# Stabilizer.net
KiCad netlist of a schematic drawn in Altium Designer
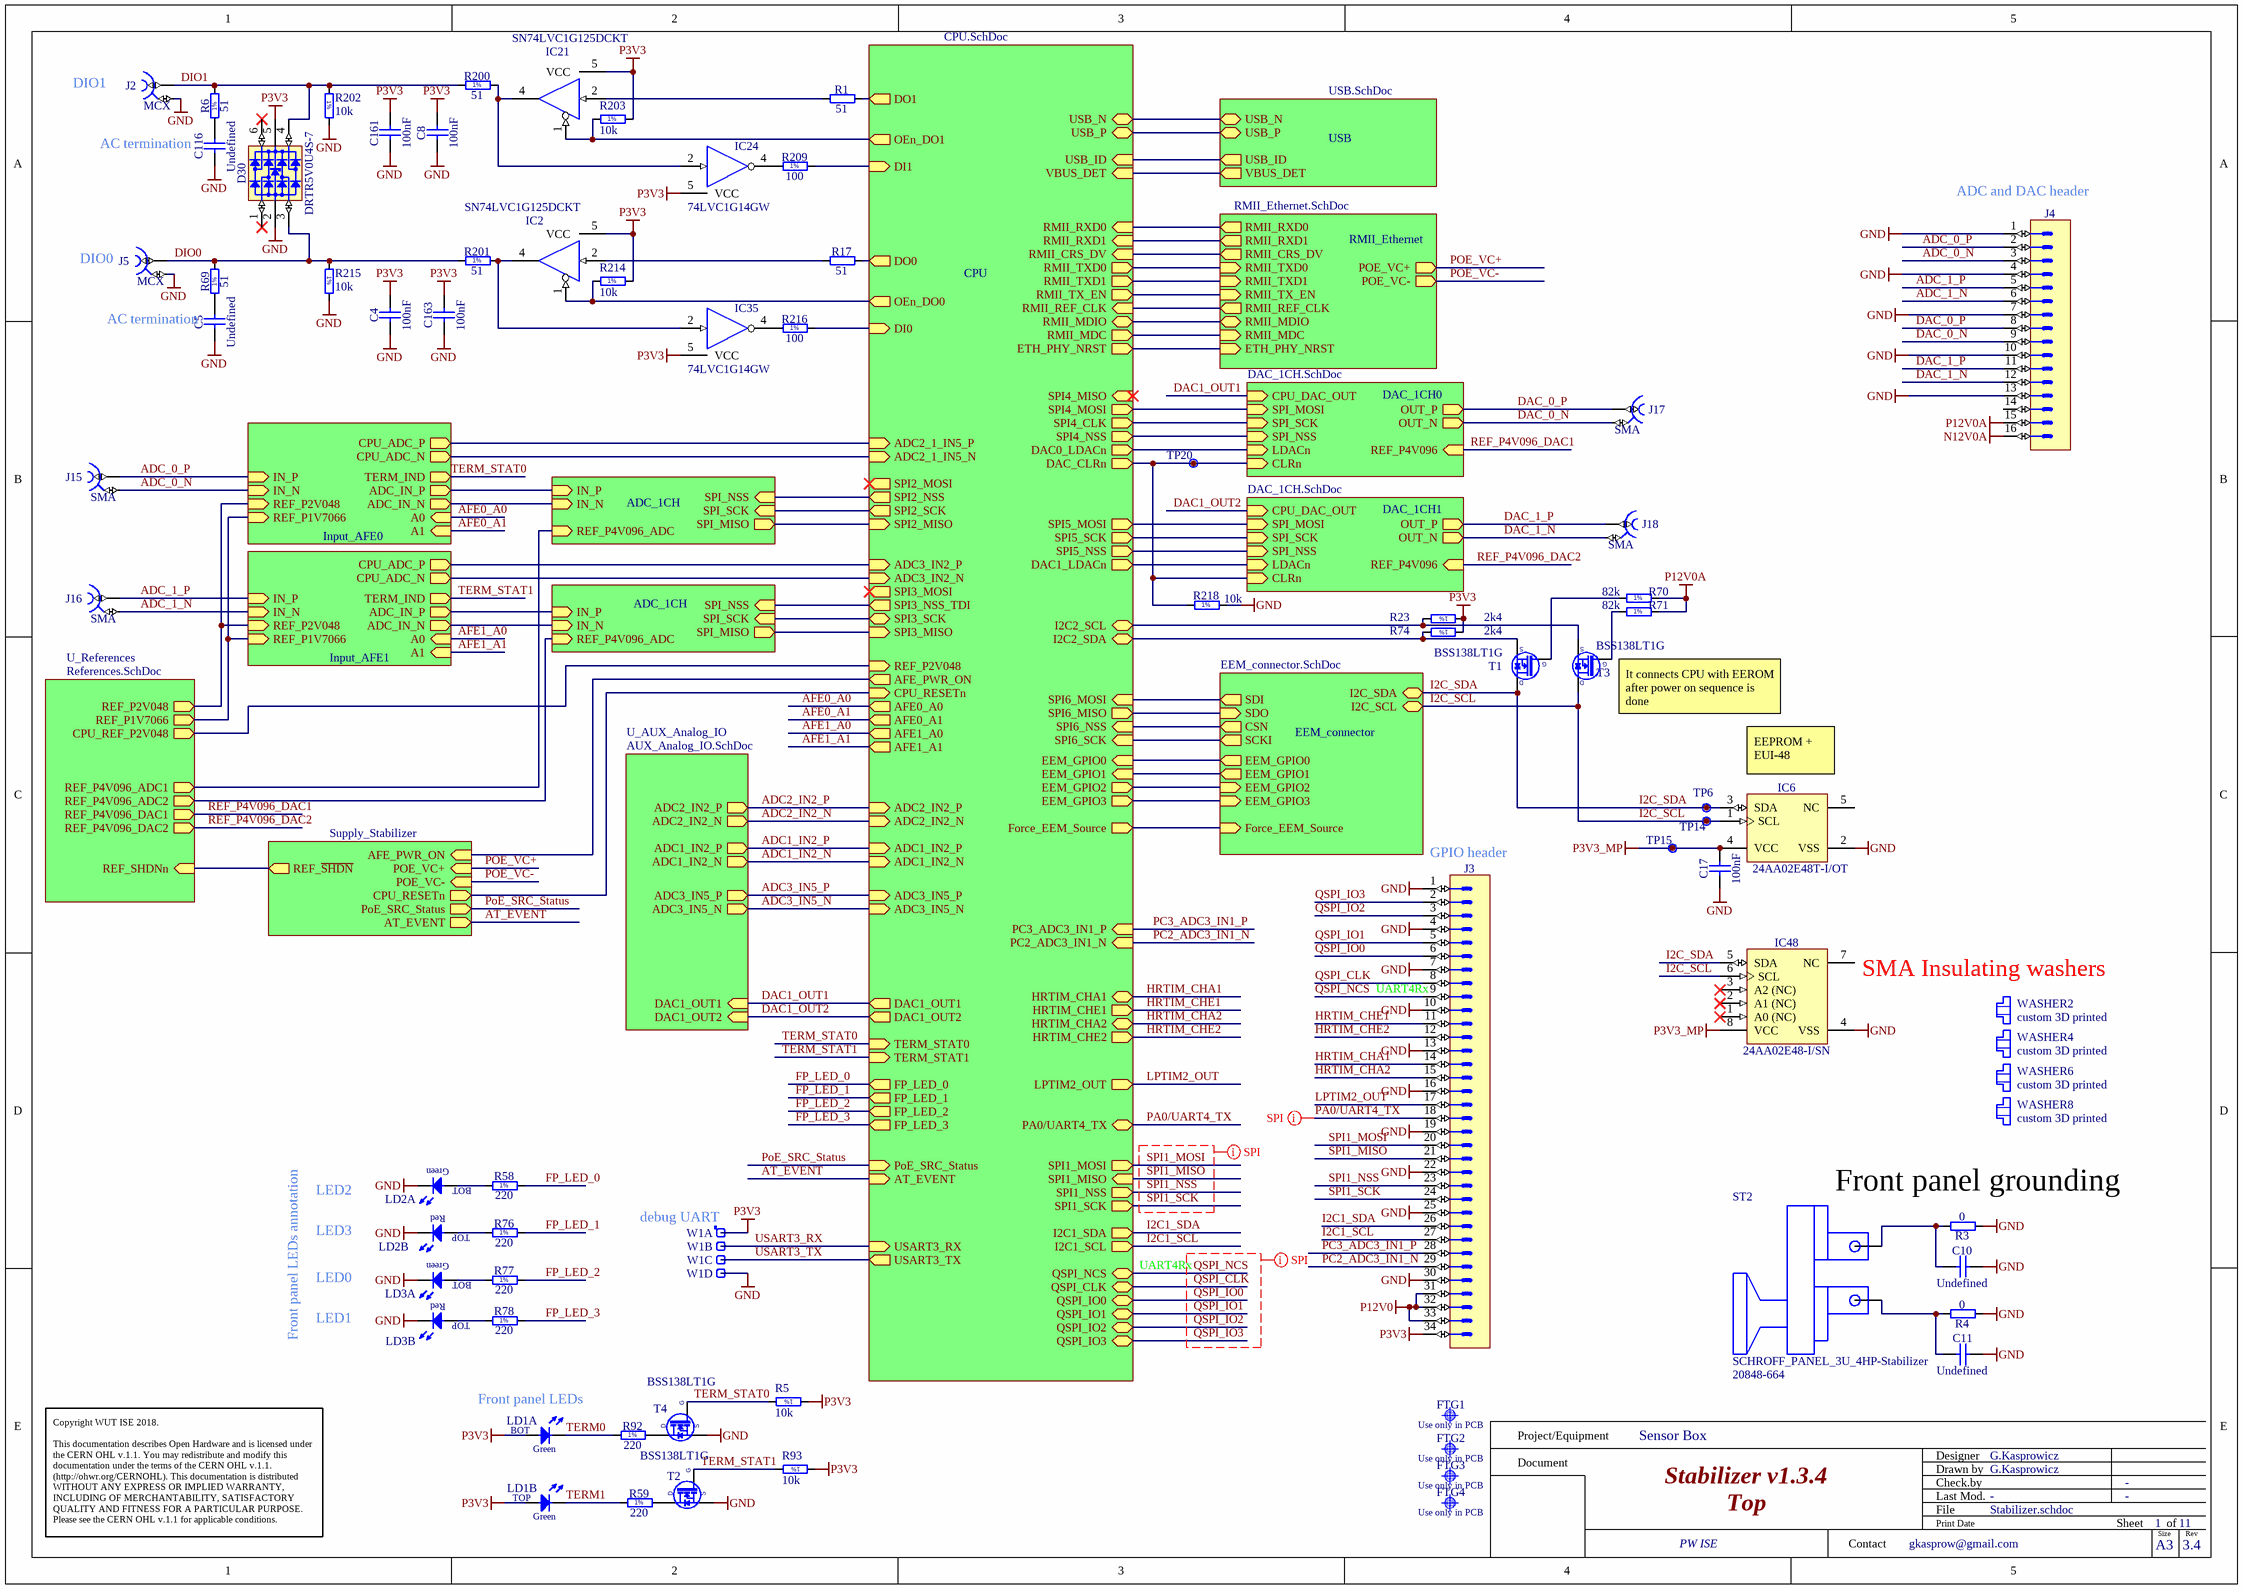
[diagram p0: Stabilizer.schdoc]

(export (version "E")
  (design (tool "Eeschema 10.0.6"))
  (components
    (comp (ref "C4")
      (value "100nF")
      (footprint "CAPC1005X55N")
      (description "Non-polarised capacitor")
      (fields
        (field (name "PART NUMBER") "CC0402_100NF_16V_10%_X7R")
        (field (name "VOLTAGE") "16V")
        (field (name "AUTHOR") "CERN DEM JLC")
      )
      (libsource (lib "Capacitors") (part "Capacitor - non polarized"))
    )
    (comp (ref "C5")
      (value "Undefined")
      (footprint "CAPC1608X90N")
      (description "Non-polarised capacitor")
      (fields (field (name "PART NUMBER") "CC0603_NO-VALUE") (field (name "AUTHOR") "CERN DEM MR"))
      (libsource (lib "Capacitors") (part "Capacitor - non polarized"))
    )
    (comp (ref "C8")
      (value "100nF")
      (footprint "CAPC1005X55N")
      (description "Non-polarised capacitor")
      (fields
        (field (name "PART NUMBER") "CC0402_100NF_16V_10%_X7R")
        (field (name "VOLTAGE") "16V")
        (field (name "AUTHOR") "CERN DEM JLC")
      )
      (libsource (lib "Capacitors") (part "Capacitor - non polarized"))
    )
    (comp (ref "C10")
      (value "Undefined")
      (footprint "CAPC2012X135N")
      (description "Non-polarised capacitor")
      (fields (field (name "PART NUMBER") "CC0805_NO-VALUE") (field (name "AUTHOR") "CERN DEM JLC"))
      (libsource (lib "Capacitors") (part "Capacitor - non polarized"))
    )
    (comp (ref "C11")
      (value "Undefined")
      (footprint "CAPC2012X135N")
      (description "Non-polarised capacitor")
      (fields (field (name "PART NUMBER") "CC0805_NO-VALUE") (field (name "AUTHOR") "CERN DEM JLC"))
      (libsource (lib "Capacitors") (part "Capacitor - non polarized"))
    )
    (comp (ref "C17")
      (value "100nF")
      (footprint "CAPC1005X55N")
      (description "Non-polarised capacitor")
      (fields
        (field (name "PART NUMBER") "CC0402_100NF_16V_10%_X5R")
        (field (name "VOLTAGE") "16V")
        (field (name "AUTHOR") "CERN DEM JLC")
      )
      (libsource (lib "Capacitors") (part "Capacitor - non polarized"))
    )
    (comp (ref "C116")
      (value "Undefined")
      (footprint "CAPC1608X90N")
      (description "Non-polarised capacitor")
      (fields (field (name "PART NUMBER") "CC0603_NO-VALUE") (field (name "AUTHOR") "CERN DEM MR"))
      (libsource (lib "Capacitors") (part "Capacitor - non polarized"))
    )
    (comp (ref "C161")
      (value "100nF")
      (footprint "CAPC1005X55N")
      (description "Non-polarised capacitor")
      (fields
        (field (name "PART NUMBER") "CC0402_100NF_16V_10%_X7R")
        (field (name "VOLTAGE") "16V")
        (field (name "AUTHOR") "CERN DEM JLC")
      )
      (libsource (lib "Capacitors") (part "Capacitor - non polarized"))
    )
    (comp (ref "C163")
      (value "100nF")
      (footprint "CAPC1005X55N")
      (description "Non-polarised capacitor")
      (fields
        (field (name "PART NUMBER") "CC0402_100NF_16V_10%_X7R")
        (field (name "VOLTAGE") "16V")
        (field (name "AUTHOR") "CERN DEM JLC")
      )
      (libsource (lib "Capacitors") (part "Capacitor - non polarized"))
    )
    (comp (ref "D30")
      (value "DRTR5V0U4S-7")
      (footprint "SOT65P210X110-6N")
      (description "Integrated Quad Ultra-Low Capacitance ESD Protection")
      (fields (field (name "MANUFACTURER") "DIODES") (field (name "AUTHOR") "GK"))
      (libsource (lib "Diodes") (part "D_TVS_DRTR5V0U4S-7"))
    )
    (comp (ref "FTG1")
      (value "Use only in PCB")
      (footprint "FIDUCIAL_TOP_C100-200")
      (description "Fiducial Target")
      (fields (field (name "PART NUMBER") "FIDUCIAL_TARGET_C100-200") (field (name "AUTHOR") "CERN DEM JLC"))
      (libsource (lib "Eletro-mechanical") (part "Fiducial Target"))
    )
    (comp (ref "FTG2")
      (value "Use only in PCB")
      (footprint "FIDUCIAL_TOP_S100-200")
      (description "Fiducial Target")
      (fields (field (name "PART NUMBER") "FIDUCIAL_TARGET_S100-200") (field (name "AUTHOR") "CERN DEM JLC"))
      (libsource (lib "Eletro-mechanical") (part "Fiducial Target"))
    )
    (comp (ref "FTG3")
      (value "Use only in PCB")
      (footprint "FIDUCIAL_TOP_S100-200")
      (description "Fiducial Target")
      (fields (field (name "PART NUMBER") "FIDUCIAL_TARGET_S100-200") (field (name "AUTHOR") "CERN DEM JLC"))
      (libsource (lib "Eletro-mechanical") (part "Fiducial Target"))
    )
    (comp (ref "FTG4")
      (value "Use only in PCB")
      (footprint "FIDUCIAL_TOP_S100-200")
      (description "Fiducial Target")
      (fields (field (name "PART NUMBER") "FIDUCIAL_TARGET_S100-200") (field (name "AUTHOR") "CERN DEM JLC"))
      (libsource (lib "Eletro-mechanical") (part "Fiducial Target"))
    )
    (comp (ref "IC2")
      (value "SN74LVC1G125DCKT")
      (footprint "SOT65P210X110-5N")
      (description "Single Bus Buffer Gate With 3-State Output")
      (fields (field (name "MANUFACTURER") "TEXAS INSTRUMENTS") (field (name "AUTHOR") "CERN DEM JLC"))
      (libsource (lib "ICs And Semiconductors") (part "741G125"))
    )
    (comp (ref "IC6")
      (value "24AA02E48T-I/OT")
      (footprint "SOT95P280X145-5N")
      (description "1.7V-5.5V, 2K I2C Serial EEPROM With EUI-48 Node Identity")
      (fields (field (name "MANUFACTURER") "MICROCHIP TECHNOLOGY") (field (name "AUTHOR") "CERN DEM MR"))
      (libsource (lib "ICs And Semiconductors") (part "24AA02E48T-I/OT"))
    )
    (comp (ref "IC21")
      (value "SN74LVC1G125DCKT")
      (footprint "SOT65P210X110-5N")
      (description "Single Bus Buffer Gate With 3-State Output")
      (fields (field (name "MANUFACTURER") "TEXAS INSTRUMENTS") (field (name "AUTHOR") "CERN DEM JLC"))
      (libsource (lib "ICs And Semiconductors") (part "741G125"))
    )
    (comp (ref "IC24")
      (value "74LVC1G14GW")
      (footprint "SOT65P212X110-5N")
      (description "Single Schmitt-Trigger Inverter")
      (fields (field (name "MANUFACTURER") "NXP SEMICONDUCTORS") (field (name "AUTHOR") "CERN DEM JLC"))
      (libsource (lib "ICs And Semiconductors") (part "741G14"))
    )
    (comp (ref "IC35")
      (value "74LVC1G14GW")
      (footprint "SOT65P212X110-5N")
      (description "Single Schmitt-Trigger Inverter")
      (fields (field (name "MANUFACTURER") "NXP SEMICONDUCTORS") (field (name "AUTHOR") "CERN DEM JLC"))
      (libsource (lib "ICs And Semiconductors") (part "741G14"))
    )
    (comp (ref "IC48")
      (value "24AA02E48-I/SN")
      (footprint "SOIC127P600X175-8N")
      (description "1.7V-5.5V, 2K I2C™ Serial EEPROMs with EUI-48™ Node Identity")
      (fields (field (name "MANUFACTURER") "MICROCHIP TECHNOLOGY") (field (name "AUTHOR") "CERN DEM MR"))
      (libsource (lib "ICS-logic") (part "MEM_24AA02E48-I/SN"))
    )
    (comp (ref "J2")
      (value "MCX")
      (footprint "AMPHENOL_919-383J-51A")
      (fields
        (field (name "PART NUMBER") "AMPHENOL_919-383J-51A")
        (field (name "MANUFACTURER") "AMPHENOL")
        (field (name "MANUFACTURER PART NUMBER") "919-383J-51A")
        (field (name "AUTHOR") "CERN DEM BC")
      )
      (libsource (lib "Connectors") (part "Coax_1Female_1Shield"))
    )
    (comp (ref "J3")
      (value "Use original!")
      (footprint "3M_N2534-6002RB")
      (description "Connector 34 Male")
      (fields
        (field (name "PART NUMBER") "Use original!  3M_N2534-6002RB")
        (field (name "MANUFACTURER") "3M")
        (field (name "AUTHOR") "CERN DEM JLC")
      )
      (libsource (lib "Connectors") (part "Connector 34 Male"))
    )
    (comp (ref "J4")
      (value "Use original!")
      (footprint "3M_N2516-6002RB")
      (description "Connector 16 Male")
      (fields
        (field (name "PART NUMBER") "Use original!  3M_N2516-6002RB")
        (field (name "MANUFACTURER") "3M")
        (field (name "AUTHOR") "CERN DEM JLC")
      )
      (libsource (lib "Connectors") (part "Connector 16 Male"))
    )
    (comp (ref "J5")
      (value "MCX")
      (footprint "AMPHENOL_919-383J-51A")
      (fields
        (field (name "PART NUMBER") "AMPHENOL_919-383J-51A")
        (field (name "MANUFACTURER") "AMPHENOL")
        (field (name "MANUFACTURER PART NUMBER") "919-383J-51A")
        (field (name "AUTHOR") "CERN DEM BC")
      )
      (libsource (lib "Connectors") (part "Coax_1Female_1Shield"))
    )
    (comp (ref "J15")
      (value "SMA")
      (footprint "DELOCK_65848")
      (description "50 Ohm Through Hole SMA Right Angle PCB Jack")
      (fields
        (field (name "PART NUMBER") "DELOCK_65848")
        (field (name "MANUFACTURER") "DELOCK")
        (field (name "AUTHOR") "GK")
      )
      (libsource (lib "Connectors") (part "CON_SMA_DELOCK_65848"))
    )
    (comp (ref "J16")
      (value "SMA")
      (footprint "DELOCK_65848")
      (description "50 Ohm Through Hole SMA Right Angle PCB Jack")
      (fields
        (field (name "PART NUMBER") "DELOCK_65848")
        (field (name "MANUFACTURER") "DELOCK")
        (field (name "AUTHOR") "GK")
      )
      (libsource (lib "Connectors") (part "CON_SMA_DELOCK_65848"))
    )
    (comp (ref "J17")
      (value "SMA")
      (footprint "DELOCK_65848")
      (description "50 Ohm Through Hole SMA Right Angle PCB Jack")
      (fields
        (field (name "PART NUMBER") "DELOCK_65848")
        (field (name "MANUFACTURER") "DELOCK")
        (field (name "AUTHOR") "GK")
      )
      (libsource (lib "") (part "CON_SMA_DELOCK_65848_1"))
    )
    (comp (ref "J18")
      (value "SMA")
      (footprint "DELOCK_65848")
      (description "50 Ohm Through Hole SMA Right Angle PCB Jack")
      (fields
        (field (name "PART NUMBER") "DELOCK_65848")
        (field (name "MANUFACTURER") "DELOCK")
        (field (name "AUTHOR") "GK")
      )
      (libsource (lib "") (part "CON_SMA_DELOCK_65848_1"))
    )
    (comp (ref "LD1")
      (value "Green/Green")
      (footprint "LED_DIALIGHT_571-0122F")
      (description "LED x2 Green 1C2A-BOT_3C4A-TOP")
      (fields
        (field (name "PART NUMBER") "LED_DIALIGHT_571-0122F")
        (field (name "MANUFACTURER") "DIALIGHT")
        (field (name "AUTHOR") "CERN DEM JLC")
      )
      (libsource (lib "ICs And Semiconductors") (part "LED x2 Green 1C2A-BOT_3C4A-TOP"))
    )
    (comp (ref "LD2")
      (value "Red/Green")
      (footprint "LED_DIALIGHT_571-0112F")
      (description "2x LED  Botom Green, Top Red")
      (fields
        (field (name "PART NUMBER") "LED_DIALIGHT_571-0112F")
        (field (name "MANUFACTURER") "DIALIGHT")
        (field (name "AUTHOR") "CERN DEM JLC")
      )
      (libsource (lib "ICs And Semiconductors") (part "LED x2 G-1C2A-BOT_R-3C4A-TOP"))
    )
    (comp (ref "LD3")
      (value "Red/Green")
      (footprint "LED_DIALIGHT_571-0112F")
      (description "2x LED  Botom Green, Top Red")
      (fields
        (field (name "PART NUMBER") "LED_DIALIGHT_571-0112F")
        (field (name "MANUFACTURER") "DIALIGHT")
        (field (name "AUTHOR") "CERN DEM JLC")
      )
      (libsource (lib "ICs And Semiconductors") (part "LED x2 G-1C2A-BOT_R-3C4A-TOP"))
    )
    (comp (ref "R1")
      (value "51")
      (footprint "RESC1005X40N")
      (description "Resistor - 1%")
      (fields
        (field (name "PART NUMBER") "R0402_51R_1%_0.0625W_100PPM")
        (field (name "POWER") "0.0625W")
        (field (name "AUTHOR") "CERN DEM JLC")
      )
      (libsource (lib "Resistors") (part "Resistor - 1%"))
    )
    (comp (ref "R3")
      (value "0")
      (footprint "RESC1608X55N")
      (description "Resistor")
      (fields
        (field (name "PART NUMBER") "R0603_0R_JUMPER")
        (field (name "MANUFACTURER") "GENERIC")
        (field (name "AUTHOR") "CERN DEM JLC")
      )
      (libsource (lib "Resistors") (part "Resistor"))
    )
    (comp (ref "R4")
      (value "0")
      (footprint "RESC1608X55N")
      (description "Resistor")
      (fields
        (field (name "PART NUMBER") "R0603_0R_JUMPER")
        (field (name "MANUFACTURER") "GENERIC")
        (field (name "AUTHOR") "CERN DEM JLC")
      )
      (libsource (lib "Resistors") (part "Resistor"))
    )
    (comp (ref "R5")
      (value "10k")
      (footprint "RESC1005X40N")
      (description "Resistor - 1%")
      (fields
        (field (name "PART NUMBER") "R0402_10K_1%_0.0625W_100PPM")
        (field (name "POWER") "0.0625W")
        (field (name "AUTHOR") "CERN DEM JLC")
      )
      (libsource (lib "Resistors") (part "Resistor - 1%"))
    )
    (comp (ref "R6")
      (value "51")
      (footprint "RESC1005X40N")
      (description "Resistor - 1%")
      (fields
        (field (name "PART NUMBER") "R0402_51R_1%_0.0625W_100PPM")
        (field (name "POWER") "0.0625W")
        (field (name "AUTHOR") "CERN DEM JLC")
      )
      (libsource (lib "Resistors") (part "Resistor - 1%"))
    )
    (comp (ref "R17")
      (value "51")
      (footprint "RESC1005X40N")
      (description "Resistor - 1%")
      (fields
        (field (name "PART NUMBER") "R0402_51R_1%_0.0625W_100PPM")
        (field (name "POWER") "0.0625W")
        (field (name "AUTHOR") "CERN DEM JLC")
      )
      (libsource (lib "Resistors") (part "Resistor - 1%"))
    )
    (comp (ref "R23")
      (value "2k4")
      (footprint "RESC1005X40N")
      (description "Resistor - 1%")
      (fields
        (field (name "PART NUMBER") "R0402_2K4_1%_0.0625W_100PPM")
        (field (name "POWER") "0.0625W")
        (field (name "AUTHOR") "CERN DEM JLC")
      )
      (libsource (lib "Resistors") (part "Resistor - 1%"))
    )
    (comp (ref "R58")
      (value "220")
      (footprint "RESC1608X55N")
      (description "Resistor - 1%")
      (fields
        (field (name "PART NUMBER") "R0603_220R_1%_0.1W_100PPM")
        (field (name "POWER") "0.1W")
        (field (name "AUTHOR") "CERN DEM JLC")
      )
      (libsource (lib "Resistors") (part "Resistor - 1%"))
    )
    (comp (ref "R59")
      (value "220")
      (footprint "RESC1608X55N")
      (description "Resistor - 1%")
      (fields
        (field (name "PART NUMBER") "R0603_220R_1%_0.1W_100PPM")
        (field (name "POWER") "0.1W")
        (field (name "AUTHOR") "CERN DEM JLC")
      )
      (libsource (lib "Resistors") (part "Resistor - 1%"))
    )
    (comp (ref "R69")
      (value "51")
      (footprint "RESC1005X40N")
      (description "Resistor - 1%")
      (fields
        (field (name "PART NUMBER") "R0402_51R_1%_0.0625W_100PPM")
        (field (name "POWER") "0.0625W")
        (field (name "AUTHOR") "CERN DEM JLC")
      )
      (libsource (lib "Resistors") (part "Resistor - 1%"))
    )
    (comp (ref "R70")
      (value "82k")
      (footprint "RESC1608X55N")
      (description "Resistor - 1%")
      (fields
        (field (name "PART NUMBER") "R0603_82K_1%_0.1W_100PPM")
        (field (name "POWER") "0.1W")
        (field (name "AUTHOR") "CERN DEM JLC")
      )
      (libsource (lib "Resistors") (part "Resistor - 1%"))
    )
    (comp (ref "R71")
      (value "82k")
      (footprint "RESC1608X55N")
      (description "Resistor - 1%")
      (fields
        (field (name "PART NUMBER") "R0603_82K_1%_0.1W_100PPM")
        (field (name "POWER") "0.1W")
        (field (name "AUTHOR") "CERN DEM JLC")
      )
      (libsource (lib "Resistors") (part "Resistor - 1%"))
    )
    (comp (ref "R74")
      (value "2k4")
      (footprint "RESC1005X40N")
      (description "Resistor - 1%")
      (fields
        (field (name "PART NUMBER") "R0402_2K4_1%_0.0625W_100PPM")
        (field (name "POWER") "0.0625W")
        (field (name "AUTHOR") "CERN DEM JLC")
      )
      (libsource (lib "Resistors") (part "Resistor - 1%"))
    )
    (comp (ref "R76")
      (value "220")
      (footprint "RESC1608X55N")
      (description "Resistor - 1%")
      (fields
        (field (name "PART NUMBER") "R0603_220R_1%_0.1W_100PPM")
        (field (name "POWER") "0.1W")
        (field (name "AUTHOR") "CERN DEM JLC")
      )
      (libsource (lib "Resistors") (part "Resistor - 1%"))
    )
    (comp (ref "R77")
      (value "220")
      (footprint "RESC1608X55N")
      (description "Resistor - 1%")
      (fields
        (field (name "PART NUMBER") "R0603_220R_1%_0.1W_100PPM")
        (field (name "POWER") "0.1W")
        (field (name "AUTHOR") "CERN DEM JLC")
      )
      (libsource (lib "Resistors") (part "Resistor - 1%"))
    )
    (comp (ref "R78")
      (value "220")
      (footprint "RESC1608X55N")
      (description "Resistor - 1%")
      (fields
        (field (name "PART NUMBER") "R0603_220R_1%_0.1W_100PPM")
        (field (name "POWER") "0.1W")
        (field (name "AUTHOR") "CERN DEM JLC")
      )
      (libsource (lib "Resistors") (part "Resistor - 1%"))
    )
    (comp (ref "R92")
      (value "220")
      (footprint "RESC1608X55N")
      (description "Resistor - 1%")
      (fields
        (field (name "PART NUMBER") "R0603_220R_1%_0.1W_100PPM")
        (field (name "POWER") "0.1W")
        (field (name "AUTHOR") "CERN DEM JLC")
      )
      (libsource (lib "Resistors") (part "Resistor - 1%"))
    )
    (comp (ref "R93")
      (value "10k")
      (footprint "RESC1005X40N")
      (description "Resistor - 1%")
      (fields
        (field (name "PART NUMBER") "R0402_10K_1%_0.0625W_100PPM")
        (field (name "POWER") "0.0625W")
        (field (name "AUTHOR") "CERN DEM JLC")
      )
      (libsource (lib "Resistors") (part "Resistor - 1%"))
    )
    (comp (ref "R200")
      (value "51")
      (footprint "RESC1005X40N")
      (description "Resistor - 1%")
      (fields
        (field (name "PART NUMBER") "R0402_51R_1%_0.0625W_100PPM")
        (field (name "POWER") "0.0625W")
        (field (name "AUTHOR") "CERN DEM JLC")
      )
      (libsource (lib "Resistors") (part "Resistor - 1%"))
    )
    (comp (ref "R201")
      (value "51")
      (footprint "RESC1005X40N")
      (description "Resistor - 1%")
      (fields
        (field (name "PART NUMBER") "R0402_51R_1%_0.0625W_100PPM")
        (field (name "POWER") "0.0625W")
        (field (name "AUTHOR") "CERN DEM JLC")
      )
      (libsource (lib "Resistors") (part "Resistor - 1%"))
    )
    (comp (ref "R202")
      (value "10k")
      (footprint "RESC1005X40N")
      (description "Resistor - 1%")
      (fields
        (field (name "PART NUMBER") "R0402_10K_1%_0.0625W_100PPM")
        (field (name "POWER") "0.0625W")
        (field (name "AUTHOR") "CERN DEM JLC")
      )
      (libsource (lib "Resistors") (part "Resistor - 1%"))
    )
    (comp (ref "R203")
      (value "10k")
      (footprint "RESC1005X40N")
      (description "Resistor - 1%")
      (fields
        (field (name "PART NUMBER") "R0402_10K_1%_0.0625W_100PPM")
        (field (name "POWER") "0.0625W")
        (field (name "AUTHOR") "CERN DEM JLC")
      )
      (libsource (lib "Resistors") (part "Resistor - 1%"))
    )
    (comp (ref "R209")
      (value "100")
      (footprint "RESC1005X40N")
      (description "Resistor - 1%")
      (fields
        (field (name "PART NUMBER") "R0402_100R_1%_0.0625W_100PPM")
        (field (name "POWER") "0.0625W")
        (field (name "AUTHOR") "CERN DEM JLC")
      )
      (libsource (lib "Resistors") (part "Resistor - 1%"))
    )
    (comp (ref "R214")
      (value "10k")
      (footprint "RESC1005X40N")
      (description "Resistor - 1%")
      (fields
        (field (name "PART NUMBER") "R0402_10K_1%_0.0625W_100PPM")
        (field (name "POWER") "0.0625W")
        (field (name "AUTHOR") "CERN DEM JLC")
      )
      (libsource (lib "Resistors") (part "Resistor - 1%"))
    )
    (comp (ref "R215")
      (value "10k")
      (footprint "RESC1005X40N")
      (description "Resistor - 1%")
      (fields
        (field (name "PART NUMBER") "R0402_10K_1%_0.0625W_100PPM")
        (field (name "POWER") "0.0625W")
        (field (name "AUTHOR") "CERN DEM JLC")
      )
      (libsource (lib "Resistors") (part "Resistor - 1%"))
    )
    (comp (ref "R216")
      (value "100")
      (footprint "RESC1005X40N")
      (description "Resistor - 1%")
      (fields
        (field (name "PART NUMBER") "R0402_100R_1%_0.0625W_100PPM")
        (field (name "POWER") "0.0625W")
        (field (name "AUTHOR") "CERN DEM JLC")
      )
      (libsource (lib "Resistors") (part "Resistor - 1%"))
    )
    (comp (ref "R218")
      (value "10k")
      (footprint "RESC1005X40N")
      (description "Resistor - 1%")
      (fields
        (field (name "PART NUMBER") "R0402_10K_1%_0.0625W_100PPM")
        (field (name "POWER") "0.0625W")
        (field (name "AUTHOR") "CERN DEM JLC")
      )
      (libsource (lib "Resistors") (part "Resistor - 1%"))
    )
    (comp (ref "ST2")
      (value "SCHROFF_PANEL_3U_4HP-Stabilizer")
      (footprint "SCHROFF_PANEL_3HP_4U - Stabilizer")
      (description "Schroff 3HP 4U EUROCARD Panel")
      (fields
        (field (name "MANUFACTURER") "Schroff")
        (field (name "MANUFACTURER PART NUMBER") "20818-017")
        (field (name "MANUFACTURER PART NUMBER 2") "20848-664")
      )
      (libsource (lib "Mechanical") (part "SCHROFF_PANEL_3U_4HP_Stabilizer"))
    )
    (comp (ref "T1")
      (value "BSS138LT1G")
      (footprint "SOT95P240X110-3N")
      (description "N-CHANNEL MOSFET WITH DIODE")
      (fields (field (name "MANUFACTURER") "ON SEMICONDUCTOR") (field (name "AUTHOR") "CERN DEM JLC"))
      (libsource (lib "ICs And Semiconductors") (part "N-MOSFET-D 1G 2S 3D"))
    )
    (comp (ref "T2")
      (value "BSS138LT1G")
      (footprint "SOT95P240X110-3N")
      (description "N-CHANNEL MOSFET WITH DIODE")
      (fields (field (name "MANUFACTURER") "ON SEMICONDUCTOR") (field (name "AUTHOR") "CERN DEM JLC"))
      (libsource (lib "ICs And Semiconductors") (part "N-MOSFET-D 1G 2S 3D"))
    )
    (comp (ref "T3")
      (value "BSS138LT1G")
      (footprint "SOT95P240X110-3N")
      (description "N-CHANNEL MOSFET WITH DIODE")
      (fields (field (name "MANUFACTURER") "ON SEMICONDUCTOR") (field (name "AUTHOR") "CERN DEM JLC"))
      (libsource (lib "ICs And Semiconductors") (part "N-MOSFET-D 1G 2S 3D"))
    )
    (comp (ref "T4")
      (value "BSS138LT1G")
      (footprint "SOT95P240X110-3N")
      (description "N-CHANNEL MOSFET WITH DIODE")
      (fields (field (name "MANUFACTURER") "ON SEMICONDUCTOR") (field (name "AUTHOR") "CERN DEM JLC"))
      (libsource (lib "ICs And Semiconductors") (part "N-MOSFET-D 1G 2S 3D"))
    )
    (comp (ref "TP6")
      (value "Test Point")
      (footprint "TPS127")
      (fields (field (name "PART NUMBER") "SMD_PAD_1.27X1.27MM") (field (name "AUTHOR") "CERN DEM JLC"))
      (libsource (lib "Eletro-mechanical") (part "Test Point"))
    )
    (comp (ref "TP14")
      (value "Test Point")
      (footprint "TPS127")
      (fields (field (name "PART NUMBER") "SMD_PAD_1.27X1.27MM") (field (name "AUTHOR") "CERN DEM JLC"))
      (libsource (lib "Eletro-mechanical") (part "Test Point"))
    )
    (comp (ref "TP15")
      (value "Test Point")
      (footprint "TPS127")
      (fields (field (name "PART NUMBER") "SMD_PAD_1.27X1.27MM") (field (name "AUTHOR") "CERN DEM JLC"))
      (libsource (lib "Eletro-mechanical") (part "Test Point"))
    )
    (comp (ref "TP20")
      (value "Test Point")
      (footprint "TPS127")
      (fields (field (name "PART NUMBER") "SMD_PAD_1.27X1.27MM") (field (name "AUTHOR") "CERN DEM JLC"))
      (libsource (lib "Eletro-mechanical") (part "Test Point"))
    )
    (comp (ref "W1")
      (value "Header 4")
      (footprint "SAMTEC_HTSW-104-23-L-S")
      (description "4 Mini Wire-Wrap Contact Strip Header")
      (fields
        (field (name "PART NUMBER") "SAMTEC_HTSW-104-23-L-S")
        (field (name "MANUFACTURER") "SAMTEC")
        (field (name "AUTHOR") "CERN DEM JLC")
      )
      (libsource (lib "Connectors") (part "Wire-Wrap Contact x4"))
    )
    (comp (ref "WASHER2")
      (value "custom 3D printed")
      (footprint "Keystone_7687")
      (description "SMA_Shoulder Washer")
      (fields (field (name "MANUFACTURER") "custom") (field (name "AUTHOR") "GK"))
      (libsource (lib "LIBRARY_SCH") (part "Keystone_7687"))
    )
    (comp (ref "WASHER4")
      (value "custom 3D printed")
      (footprint "Keystone_7687")
      (description "SMA_Shoulder Washer")
      (fields (field (name "MANUFACTURER") "custom") (field (name "AUTHOR") "GK"))
      (libsource (lib "LIBRARY_SCH") (part "Keystone_7687"))
    )
    (comp (ref "WASHER6")
      (value "custom 3D printed")
      (footprint "Keystone_7687")
      (description "SMA_Shoulder Washer")
      (fields (field (name "MANUFACTURER") "custom") (field (name "AUTHOR") "GK"))
      (libsource (lib "LIBRARY_SCH") (part "Keystone_7687"))
    )
    (comp (ref "WASHER8")
      (value "custom 3D printed")
      (footprint "Keystone_7687")
      (description "SMA_Shoulder Washer")
      (fields (field (name "MANUFACTURER") "custom") (field (name "AUTHOR") "GK"))
      (libsource (lib "LIBRARY_SCH") (part "Keystone_7687"))
    )
  )
  (nets
    (net (code "7") (name "/ADC_0_N") (class "Default")
      (node (ref "J15") (pin "2") (pinfunction "2_2") (pintype "bidirectional"))
      (node (ref "J4") (pin "3") (pinfunction "3_3") (pintype "bidirectional"))
    )
    (net (code "8") (name "/ADC_0_P") (class "Default")
      (node (ref "J15") (pin "1") (pinfunction "1_1") (pintype "bidirectional"))
      (node (ref "J4") (pin "2") (pinfunction "2_2") (pintype "bidirectional"))
    )
    (net (code "9") (name "/ADC_1_N") (class "Default")
      (node (ref "J16") (pin "2") (pinfunction "2_2") (pintype "bidirectional"))
      (node (ref "J4") (pin "6") (pinfunction "6_6") (pintype "bidirectional"))
    )
    (net (code "10") (name "/ADC_1_P") (class "Default")
      (node (ref "J16") (pin "1") (pinfunction "1_1") (pintype "bidirectional"))
      (node (ref "J4") (pin "5") (pinfunction "5_5") (pintype "bidirectional"))
    )
    (net (code "32") (name "/DAC_0_N") (class "Default")
      (node (ref "J17") (pin "2") (pinfunction "2_2") (pintype "bidirectional"))
      (node (ref "J4") (pin "9") (pinfunction "9_9") (pintype "bidirectional"))
    )
    (net (code "33") (name "/DAC_0_P") (class "Default")
      (node (ref "J17") (pin "1") (pinfunction "1_1") (pintype "bidirectional"))
      (node (ref "J4") (pin "8") (pinfunction "8_8") (pintype "bidirectional"))
    )
    (net (code "34") (name "/DAC_1_N") (class "Default")
      (node (ref "J18") (pin "2") (pinfunction "2_2") (pintype "bidirectional"))
      (node (ref "J4") (pin "12") (pinfunction "12_12") (pintype "bidirectional"))
    )
    (net (code "35") (name "/DAC_1_P") (class "Default")
      (node (ref "J18") (pin "1") (pinfunction "1_1") (pintype "bidirectional"))
      (node (ref "J4") (pin "11") (pinfunction "11_11") (pintype "bidirectional"))
    )
    (net (code "36") (name "/DAC_CLRn") (class "Default")
      (node (ref "R218") (pin "1") (pinfunction "1_1") (pintype "passive"))
      (node (ref "TP20") (pin "1") (pinfunction "1_1") (pintype "bidirectional"))
    )
    (net (code "37") (name "/DI0") (class "Default")
      (node (ref "R216") (pin "2") (pinfunction "2_2") (pintype "passive"))
    )
    (net (code "38") (name "/DI1") (class "Default")
      (node (ref "R209") (pin "2") (pinfunction "2_2") (pintype "passive"))
    )
    (net (code "39") (name "/DIO0") (class "Default")
      (node (ref "D30") (pin "3") (pinfunction "I/O2_3") (pintype "bidirectional"))
      (node (ref "J5") (pin "1") (pinfunction "1_1") (pintype "bidirectional"))
      (node (ref "R201") (pin "1") (pinfunction "1_1") (pintype "passive"))
      (node (ref "R215") (pin "1") (pinfunction "1_1") (pintype "passive"))
      (node (ref "R69") (pin "2") (pinfunction "2_2") (pintype "passive"))
    )
    (net (code "40") (name "/DIO1") (class "Default")
      (node (ref "D30") (pin "4") (pinfunction "I/O3_4") (pintype "bidirectional"))
      (node (ref "J2") (pin "1") (pinfunction "1_1") (pintype "bidirectional"))
      (node (ref "R200") (pin "1") (pinfunction "1_1") (pintype "passive"))
      (node (ref "R202") (pin "1") (pinfunction "1_1") (pintype "passive"))
      (node (ref "R6") (pin "2") (pinfunction "2_2") (pintype "passive"))
    )
    (net (code "41") (name "/DO0") (class "Default")
      (node (ref "R17") (pin "2") (pinfunction "2_2") (pintype "passive"))
    )
    (net (code "42") (name "/DO1") (class "Default")
      (node (ref "R1") (pin "2") (pinfunction "2_2") (pintype "passive"))
    )
    (net (code "48") (name "/FP_LED_0") (class "Default")
      (node (ref "R58") (pin "2") (pinfunction "2_2") (pintype "passive"))
    )
    (net (code "49") (name "/FP_LED_1") (class "Default")
      (node (ref "R76") (pin "2") (pinfunction "2_2") (pintype "passive"))
    )
    (net (code "50") (name "/FP_LED_2") (class "Default")
      (node (ref "R77") (pin "2") (pinfunction "2_2") (pintype "passive"))
    )
    (net (code "51") (name "/FP_LED_3") (class "Default")
      (node (ref "R78") (pin "2") (pinfunction "2_2") (pintype "passive"))
    )
    (net (code "53") (name "/HRTIM_CHA1") (class "Default")
      (node (ref "J3") (pin "14") (pinfunction "14_14") (pintype "bidirectional"))
    )
    (net (code "54") (name "/HRTIM_CHA2") (class "Default")
      (node (ref "J3") (pin "15") (pinfunction "15_15") (pintype "bidirectional"))
    )
    (net (code "55") (name "/HRTIM_CHE1") (class "Default")
      (node (ref "J3") (pin "11") (pinfunction "11_11") (pintype "bidirectional"))
    )
    (net (code "56") (name "/HRTIM_CHE2") (class "Default")
      (node (ref "J3") (pin "12") (pinfunction "12_12") (pintype "bidirectional"))
    )
    (net (code "57") (name "/I2C1_SCL") (class "Default")
      (node (ref "J3") (pin "27") (pinfunction "27_27") (pintype "bidirectional"))
    )
    (net (code "58") (name "/I2C1_SDA") (class "Default")
      (node (ref "J3") (pin "26") (pinfunction "26_26") (pintype "bidirectional"))
    )
    (net (code "59") (name "/I2C2_SCL") (class "Default")
      (node (ref "R23") (pin "2") (pinfunction "2_2") (pintype "passive"))
      (node (ref "T3") (pin "2") (pinfunction "S_2") (pintype "passive"))
    )
    (net (code "60") (name "/I2C2_SDA") (class "Default")
      (node (ref "R74") (pin "2") (pinfunction "2_2") (pintype "passive"))
      (node (ref "T1") (pin "2") (pinfunction "S_2") (pintype "passive"))
    )
    (net (code "61") (name "/I2C_SCL") (class "Default")
      (node (ref "IC48") (pin "6") (pinfunction "SCL_6") (pintype "input"))
      (node (ref "IC6") (pin "1") (pinfunction "SCL_1") (pintype "input"))
      (node (ref "T3") (pin "3") (pinfunction "D_3") (pintype "passive"))
      (node (ref "TP14") (pin "1") (pinfunction "1_1") (pintype "bidirectional"))
    )
    (net (code "62") (name "/I2C_SDA") (class "Default")
      (node (ref "IC48") (pin "5") (pinfunction "SDA_5") (pintype "bidirectional"))
      (node (ref "IC6") (pin "3") (pinfunction "SDA_3") (pintype "bidirectional"))
      (node (ref "T1") (pin "3") (pinfunction "D_3") (pintype "passive"))
      (node (ref "TP6") (pin "1") (pinfunction "1_1") (pintype "bidirectional"))
    )
    (net (code "63") (name "/LPTIM2_OUT") (class "Default")
      (node (ref "J3") (pin "17") (pinfunction "17_17") (pintype "bidirectional"))
    )
    (net (code "64") (name "/OEn_DO0") (class "Default")
      (node (ref "IC2") (pin "1") (pinfunction "~{G}_1") (pintype "input"))
      (node (ref "R214") (pin "1") (pinfunction "1_1") (pintype "passive"))
    )
    (net (code "65") (name "/OEn_DO1") (class "Default")
      (node (ref "IC21") (pin "1") (pinfunction "~{G}_1") (pintype "input"))
      (node (ref "R203") (pin "1") (pinfunction "1_1") (pintype "passive"))
    )
    (net (code "66") (name "/PA0{slash}UART4_TX") (class "Default")
      (node (ref "J3") (pin "18") (pinfunction "18_18") (pintype "bidirectional"))
    )
    (net (code "67") (name "/PC2_ADC3_IN1_N") (class "Default")
      (node (ref "J3") (pin "29") (pinfunction "29_29") (pintype "bidirectional"))
    )
    (net (code "68") (name "/PC3_ADC3_IN1_P") (class "Default")
      (node (ref "J3") (pin "28") (pinfunction "28_28") (pintype "bidirectional"))
    )
    (net (code "72") (name "/QSPI_CLK") (class "Default")
      (node (ref "J3") (pin "8") (pinfunction "8_8") (pintype "bidirectional"))
    )
    (net (code "73") (name "/QSPI_IO0") (class "Default")
      (node (ref "J3") (pin "6") (pinfunction "6_6") (pintype "bidirectional"))
    )
    (net (code "74") (name "/QSPI_IO1") (class "Default")
      (node (ref "J3") (pin "5") (pinfunction "5_5") (pintype "bidirectional"))
    )
    (net (code "75") (name "/QSPI_IO2") (class "Default")
      (node (ref "J3") (pin "3") (pinfunction "3_3") (pintype "bidirectional"))
    )
    (net (code "76") (name "/QSPI_IO3") (class "Default")
      (node (ref "J3") (pin "2") (pinfunction "2_2") (pintype "bidirectional"))
    )
    (net (code "77") (name "/QSPI_NCS") (class "Default")
      (node (ref "J3") (pin "9") (pinfunction "9_9") (pintype "bidirectional"))
    )
    (net (code "96") (name "/SPI1_MISO") (class "Default")
      (node (ref "J3") (pin "21") (pinfunction "21_21") (pintype "bidirectional"))
    )
    (net (code "97") (name "/SPI1_MOSI") (class "Default")
      (node (ref "J3") (pin "20") (pinfunction "20_20") (pintype "bidirectional"))
    )
    (net (code "98") (name "/SPI1_NSS") (class "Default")
      (node (ref "J3") (pin "23") (pinfunction "23_23") (pintype "bidirectional"))
    )
    (net (code "99") (name "/SPI1_SCK") (class "Default")
      (node (ref "J3") (pin "24") (pinfunction "24_24") (pintype "bidirectional"))
    )
    (net (code "116") (name "/TERM0") (class "Default")
      (node (ref "LD1") (pin "1") (pinfunction "C_1") (pintype "passive"))
      (node (ref "R92") (pin "1") (pinfunction "1_1") (pintype "passive"))
    )
    (net (code "117") (name "/TERM1") (class "Default")
      (node (ref "LD1") (pin "3") (pinfunction "C_3") (pintype "passive"))
      (node (ref "R59") (pin "1") (pinfunction "1_1") (pintype "passive"))
    )
    (net (code "118") (name "/TERM_STAT0") (class "Default")
      (node (ref "R5") (pin "2") (pinfunction "2_2") (pintype "passive"))
      (node (ref "T4") (pin "1") (pinfunction "G_1") (pintype "passive"))
    )
    (net (code "119") (name "/TERM_STAT1") (class "Default")
      (node (ref "R93") (pin "2") (pinfunction "2_2") (pintype "passive"))
      (node (ref "T2") (pin "1") (pinfunction "G_1") (pintype "passive"))
    )
    (net (code "120") (name "/USART3_RX") (class "Default")
      (node (ref "W1") (pin "2") (pinfunction "2_2") (pintype "bidirectional"))
    )
    (net (code "121") (name "/USART3_TX") (class "Default")
      (node (ref "W1") (pin "3") (pinfunction "3_3") (pintype "bidirectional"))
    )
    (net (code "126") (name "GND") (class "Default")
      (node (ref "C10") (pin "2") (pinfunction "2_2") (pintype "passive"))
      (node (ref "C11") (pin "2") (pinfunction "2_2") (pintype "passive"))
      (node (ref "C116") (pin "1") (pinfunction "1_1") (pintype "passive"))
      (node (ref "C161") (pin "1") (pinfunction "1_1") (pintype "passive"))
      (node (ref "C163") (pin "1") (pinfunction "1_1") (pintype "passive"))
      (node (ref "C17") (pin "1") (pinfunction "1_1") (pintype "passive"))
      (node (ref "C4") (pin "1") (pinfunction "1_1") (pintype "passive"))
      (node (ref "C5") (pin "1") (pinfunction "1_1") (pintype "passive"))
      (node (ref "C8") (pin "1") (pinfunction "1_1") (pintype "passive"))
      (node (ref "D30") (pin "2") (pinfunction "GND_2") (pintype "power_in"))
      (node (ref "IC2") (pin "3") (pinfunction "GND_3") (pintype "power_in"))
      (node (ref "IC21") (pin "3") (pinfunction "GND_3") (pintype "power_in"))
      (node (ref "IC24") (pin "3") (pinfunction "GND_3") (pintype "power_in"))
      (node (ref "IC35") (pin "3") (pinfunction "GND_3") (pintype "power_in"))
      (node (ref "IC48") (pin "4") (pinfunction "VSS_4") (pintype "power_in"))
      (node (ref "IC6") (pin "2") (pinfunction "VSS_2") (pintype "power_in"))
      (node (ref "J2") (pin "2") (pinfunction "2_2") (pintype "bidirectional"))
      (node (ref "J3") (pin "1") (pinfunction "1_1") (pintype "bidirectional"))
      (node (ref "J3") (pin "10") (pinfunction "10_10") (pintype "bidirectional"))
      (node (ref "J3") (pin "13") (pinfunction "13_13") (pintype "bidirectional"))
      (node (ref "J3") (pin "16") (pinfunction "16_16") (pintype "bidirectional"))
      (node (ref "J3") (pin "19") (pinfunction "19_19") (pintype "bidirectional"))
      (node (ref "J3") (pin "22") (pinfunction "22_22") (pintype "bidirectional"))
      (node (ref "J3") (pin "25") (pinfunction "25_25") (pintype "bidirectional"))
      (node (ref "J3") (pin "30") (pinfunction "30_30") (pintype "bidirectional"))
      (node (ref "J3") (pin "4") (pinfunction "4_4") (pintype "bidirectional"))
      (node (ref "J3") (pin "7") (pinfunction "7_7") (pintype "bidirectional"))
      (node (ref "J4") (pin "1") (pinfunction "1_1") (pintype "bidirectional"))
      (node (ref "J4") (pin "10") (pinfunction "10_10") (pintype "bidirectional"))
      (node (ref "J4") (pin "13") (pinfunction "13_13") (pintype "bidirectional"))
      (node (ref "J4") (pin "4") (pinfunction "4_4") (pintype "bidirectional"))
      (node (ref "J4") (pin "7") (pinfunction "7_7") (pintype "bidirectional"))
      (node (ref "J5") (pin "2") (pinfunction "2_2") (pintype "bidirectional"))
      (node (ref "LD2") (pin "1") (pinfunction "C_1") (pintype "passive"))
      (node (ref "LD2") (pin "3") (pinfunction "C_3") (pintype "passive"))
      (node (ref "LD3") (pin "1") (pinfunction "C_1") (pintype "passive"))
      (node (ref "LD3") (pin "3") (pinfunction "C_3") (pintype "passive"))
      (node (ref "R202") (pin "2") (pinfunction "2_2") (pintype "passive"))
      (node (ref "R215") (pin "2") (pinfunction "2_2") (pintype "passive"))
      (node (ref "R218") (pin "2") (pinfunction "2_2") (pintype "passive"))
      (node (ref "R3") (pin "1") (pinfunction "1_1") (pintype "passive"))
      (node (ref "R4") (pin "1") (pinfunction "1_1") (pintype "passive"))
      (node (ref "T2") (pin "2") (pinfunction "S_2") (pintype "passive"))
      (node (ref "T4") (pin "2") (pinfunction "S_2") (pintype "passive"))
      (node (ref "W1") (pin "4") (pinfunction "4_4") (pintype "bidirectional"))
    )
    (net (code "127") (name "N12V0A") (class "Default")
      (node (ref "J4") (pin "16") (pinfunction "16_16") (pintype "bidirectional"))
    )
    (net (code "128") (name "Net-(C5-Pad2)") (class "Default")
      (node (ref "C5") (pin "2") (pinfunction "2_2") (pintype "passive"))
      (node (ref "R69") (pin "1") (pinfunction "1_1") (pintype "passive"))
    )
    (net (code "129") (name "Net-(C10-Pad1)") (class "Default")
      (node (ref "C10") (pin "1") (pinfunction "1_1") (pintype "passive"))
      (node (ref "R3") (pin "2") (pinfunction "2_2") (pintype "passive"))
      (node (ref "ST2") (pin "1") (pinfunction "1_1") (pintype "passive"))
    )
    (net (code "130") (name "Net-(C11-Pad1)") (class "Default")
      (node (ref "C11") (pin "1") (pinfunction "1_1") (pintype "passive"))
      (node (ref "R4") (pin "2") (pinfunction "2_2") (pintype "passive"))
      (node (ref "ST2") (pin "0") (pinfunction "0_0") (pintype "passive"))
    )
    (net (code "131") (name "Net-(C116-Pad2)") (class "Default")
      (node (ref "C116") (pin "2") (pinfunction "2_2") (pintype "passive"))
      (node (ref "R6") (pin "1") (pinfunction "1_1") (pintype "passive"))
    )
    (net (code "132") (name "Net-(IC2-IN)") (class "Default")
      (node (ref "IC2") (pin "2") (pinfunction "IN_2") (pintype "input"))
      (node (ref "R17") (pin "1") (pinfunction "1_1") (pintype "passive"))
    )
    (net (code "133") (name "Net-(IC2-OUT)") (class "Default")
      (node (ref "IC2") (pin "4") (pinfunction "OUT_4") (pintype "tri_state"))
      (node (ref "IC35") (pin "2") (pinfunction "IN_2") (pintype "input"))
      (node (ref "R201") (pin "2") (pinfunction "2_2") (pintype "passive"))
    )
    (net (code "134") (name "Net-(IC21-IN)") (class "Default")
      (node (ref "IC21") (pin "2") (pinfunction "IN_2") (pintype "input"))
      (node (ref "R1") (pin "1") (pinfunction "1_1") (pintype "passive"))
    )
    (net (code "135") (name "Net-(IC21-OUT)") (class "Default")
      (node (ref "IC21") (pin "4") (pinfunction "OUT_4") (pintype "tri_state"))
      (node (ref "IC24") (pin "2") (pinfunction "IN_2") (pintype "input"))
      (node (ref "R200") (pin "2") (pinfunction "2_2") (pintype "passive"))
    )
    (net (code "136") (name "Net-(IC24-OUT)") (class "Default")
      (node (ref "IC24") (pin "4") (pinfunction "OUT_4") (pintype "open_collector"))
      (node (ref "R209") (pin "1") (pinfunction "1_1") (pintype "passive"))
    )
    (net (code "137") (name "Net-(IC35-OUT)") (class "Default")
      (node (ref "IC35") (pin "4") (pinfunction "OUT_4") (pintype "open_collector"))
      (node (ref "R216") (pin "1") (pinfunction "1_1") (pintype "passive"))
    )
    (net (code "138") (name "Net-(LD2A-A)") (class "Default")
      (node (ref "LD2") (pin "2") (pinfunction "A_2") (pintype "passive"))
      (node (ref "R58") (pin "1") (pinfunction "1_1") (pintype "passive"))
    )
    (net (code "139") (name "Net-(LD2B-A)") (class "Default")
      (node (ref "LD2") (pin "4") (pinfunction "A_4") (pintype "passive"))
      (node (ref "R76") (pin "1") (pinfunction "1_1") (pintype "passive"))
    )
    (net (code "140") (name "Net-(LD3A-A)") (class "Default")
      (node (ref "LD3") (pin "2") (pinfunction "A_2") (pintype "passive"))
      (node (ref "R77") (pin "1") (pinfunction "1_1") (pintype "passive"))
    )
    (net (code "141") (name "Net-(LD3B-A)") (class "Default")
      (node (ref "LD3") (pin "4") (pinfunction "A_4") (pintype "passive"))
      (node (ref "R78") (pin "1") (pinfunction "1_1") (pintype "passive"))
    )
    (net (code "142") (name "Net-(T1-G)") (class "Default")
      (node (ref "R70") (pin "1") (pinfunction "1_1") (pintype "passive"))
      (node (ref "T1") (pin "1") (pinfunction "G_1") (pintype "passive"))
    )
    (net (code "143") (name "Net-(T2-D)") (class "Default")
      (node (ref "R59") (pin "2") (pinfunction "2_2") (pintype "passive"))
      (node (ref "T2") (pin "3") (pinfunction "D_3") (pintype "passive"))
    )
    (net (code "144") (name "Net-(T3-G)") (class "Default")
      (node (ref "R71") (pin "1") (pinfunction "1_1") (pintype "passive"))
      (node (ref "T3") (pin "1") (pinfunction "G_1") (pintype "passive"))
    )
    (net (code "145") (name "Net-(T4-D)") (class "Default")
      (node (ref "R92") (pin "2") (pinfunction "2_2") (pintype "passive"))
      (node (ref "T4") (pin "3") (pinfunction "D_3") (pintype "passive"))
    )
    (net (code "146") (name "P3V3") (class "Default")
      (node (ref "C161") (pin "2") (pinfunction "2_2") (pintype "passive"))
      (node (ref "C163") (pin "2") (pinfunction "2_2") (pintype "passive"))
      (node (ref "C4") (pin "2") (pinfunction "2_2") (pintype "passive"))
      (node (ref "C8") (pin "2") (pinfunction "2_2") (pintype "passive"))
      (node (ref "D30") (pin "5") (pinfunction "VBUS_5") (pintype "power_in"))
      (node (ref "IC2") (pin "5") (pinfunction "VCC_5") (pintype "power_in"))
      (node (ref "IC21") (pin "5") (pinfunction "VCC_5") (pintype "power_in"))
      (node (ref "IC24") (pin "5") (pinfunction "VCC_5") (pintype "power_in"))
      (node (ref "IC35") (pin "5") (pinfunction "VCC_5") (pintype "power_in"))
      (node (ref "J3") (pin "34") (pinfunction "34_34") (pintype "bidirectional"))
      (node (ref "LD1") (pin "2") (pinfunction "A_2") (pintype "passive"))
      (node (ref "LD1") (pin "4") (pinfunction "A_4") (pintype "passive"))
      (node (ref "R203") (pin "2") (pinfunction "2_2") (pintype "passive"))
      (node (ref "R214") (pin "2") (pinfunction "2_2") (pintype "passive"))
      (node (ref "R23") (pin "1") (pinfunction "1_1") (pintype "passive"))
      (node (ref "R5") (pin "1") (pinfunction "1_1") (pintype "passive"))
      (node (ref "R74") (pin "1") (pinfunction "1_1") (pintype "passive"))
      (node (ref "R93") (pin "1") (pinfunction "1_1") (pintype "passive"))
      (node (ref "W1") (pin "1") (pinfunction "1_1") (pintype "bidirectional"))
    )
    (net (code "147") (name "P3V3_MP") (class "Default")
      (node (ref "C17") (pin "2") (pinfunction "2_2") (pintype "passive"))
      (node (ref "IC48") (pin "8") (pinfunction "VCC_8") (pintype "power_in"))
      (node (ref "IC6") (pin "4") (pinfunction "VCC_4") (pintype "power_in"))
      (node (ref "TP15") (pin "1") (pinfunction "1_1") (pintype "bidirectional"))
    )
    (net (code "148") (name "P12V0") (class "Default")
      (node (ref "J3") (pin "31") (pinfunction "31_31") (pintype "bidirectional"))
      (node (ref "J3") (pin "32") (pinfunction "32_32") (pintype "bidirectional"))
      (node (ref "J3") (pin "33") (pinfunction "33_33") (pintype "bidirectional"))
    )
    (net (code "149") (name "P12V0A") (class "Default")
      (node (ref "J4") (pin "15") (pinfunction "15_15") (pintype "bidirectional"))
      (node (ref "R70") (pin "2") (pinfunction "2_2") (pintype "passive"))
      (node (ref "R71") (pin "2") (pinfunction "2_2") (pintype "passive"))
    )
    (net (code "150") (name "unconnected-(D30-I{slash}O1-Pad1)") (class "Default")
      (node (ref "D30") (pin "1") (pinfunction "I/O1_1") (pintype "bidirectional+no_connect"))
    )
    (net (code "151") (name "unconnected-(D30-I{slash}O4-Pad6)") (class "Default")
      (node (ref "D30") (pin "6") (pinfunction "I/O4_6") (pintype "bidirectional+no_connect"))
    )
    (net (code "152") (name "unconnected-(IC6-NC-Pad5)") (class "Default")
      (node (ref "IC6") (pin "5") (pinfunction "NC_5") (pintype "passive"))
    )
    (net (code "153") (name "unconnected-(IC48-A0_(NC)-Pad1)") (class "Default")
      (node (ref "IC48") (pin "1") (pinfunction "A0_(NC)_1") (pintype "input+no_connect"))
    )
    (net (code "154") (name "unconnected-(IC48-A1_(NC)-Pad2)") (class "Default")
      (node (ref "IC48") (pin "2") (pinfunction "A1_(NC)_2") (pintype "input+no_connect"))
    )
    (net (code "155") (name "unconnected-(IC48-A2_(NC)-Pad3)") (class "Default")
      (node (ref "IC48") (pin "3") (pinfunction "A2_(NC)_3") (pintype "input+no_connect"))
    )
    (net (code "156") (name "unconnected-(IC48-NC-Pad7)") (class "Default")
      (node (ref "IC48") (pin "7") (pinfunction "NC_7") (pintype "passive"))
    )
    (net (code "157") (name "unconnected-(J4-Pad14)") (class "Default")
      (node (ref "J4") (pin "14") (pinfunction "14_14") (pintype "bidirectional"))
    )
  )
)
